# PM12_CDCE62005.net
KiCad netlist of a schematic drawn in Altium Designer
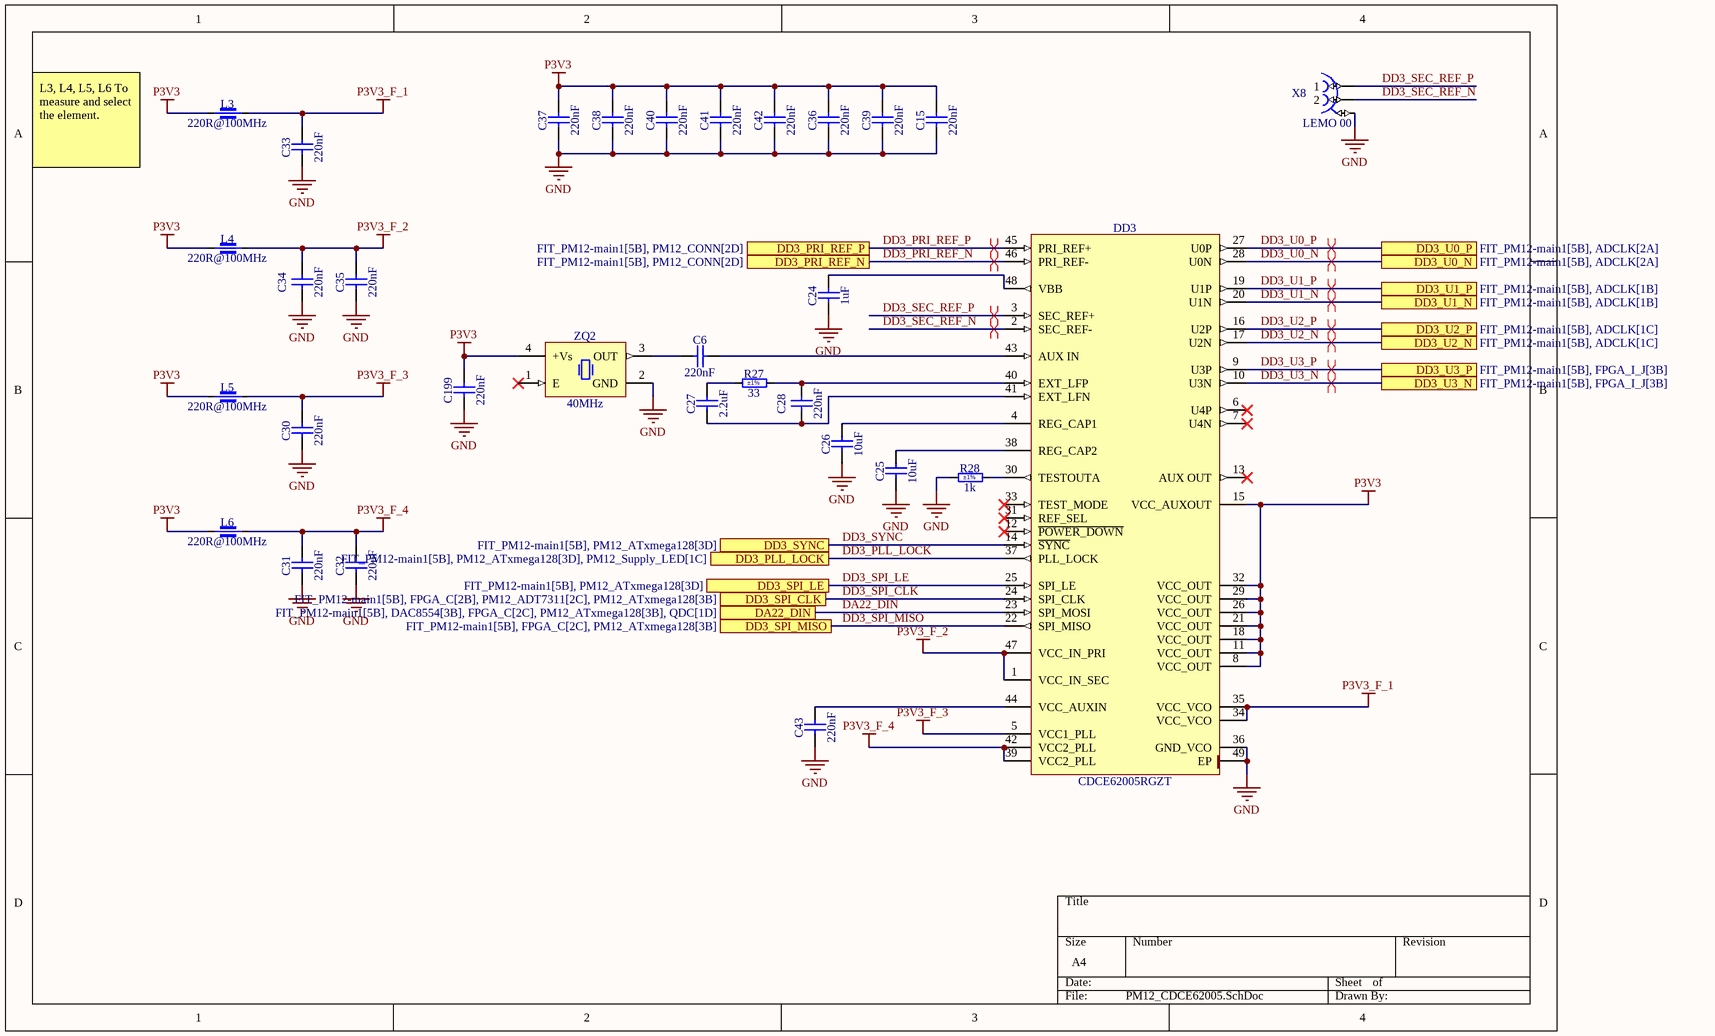
[diagram p0: PM12_CDCE62005.SchDoc]

(export (version "E")
  (design (tool "Eeschema 10.0.6"))
  (components
    (comp (ref "C6")
      (value "220nF")
      (footprint "CAPC2012X135N")
      (description "Non-polarised capacitor")
      (fields
        (field (name "PART NUMBER") "CC0805_220NF_50V_10%_X7R")
        (field (name "VOLTAGE") "50V")
        (field (name "AUTHOR") "CERN DEM JLC")
      )
      (libsource (lib "Capacitors") (part "Capacitor - non polarized"))
    )
    (comp (ref "C15")
      (value "220nF")
      (footprint "CAPC2012X135N")
      (description "Non-polarised capacitor")
      (fields
        (field (name "PART NUMBER") "CC0805_220NF_50V_10%_X7R")
        (field (name "VOLTAGE") "50V")
        (field (name "AUTHOR") "CERN DEM JLC")
      )
      (libsource (lib "Capacitors") (part "Capacitor - non polarized"))
    )
    (comp (ref "C24")
      (value "1uF")
      (footprint "CAPC2012X140N")
      (description "Non-polarised capacitor")
      (fields
        (field (name "PART NUMBER") "CC0805_1UF_25V_10%_X7R")
        (field (name "VOLTAGE") "25V")
        (field (name "AUTHOR") "CERN DEM JLC")
      )
      (libsource (lib "Capacitors") (part "Capacitor - non polarized"))
    )
    (comp (ref "C25")
      (value "10uF")
      (footprint "CAPC2012X145N")
      (description "Non-polarised capacitor")
      (fields
        (field (name "PART NUMBER") "CC0805_10UF_25V_10%_X7R")
        (field (name "VOLTAGE") "25V")
        (field (name "AUTHOR") "CERN DEM HF")
      )
      (libsource (lib "Capacitors") (part "Capacitor - non polarized"))
    )
    (comp (ref "C26")
      (value "10uF")
      (footprint "CAPC2012X145N")
      (description "Non-polarised capacitor")
      (fields
        (field (name "PART NUMBER") "CC0805_10UF_25V_10%_X7R")
        (field (name "VOLTAGE") "25V")
        (field (name "AUTHOR") "CERN DEM HF")
      )
      (libsource (lib "Capacitors") (part "Capacitor - non polarized"))
    )
    (comp (ref "C27")
      (value "2.2uF")
      (footprint "CAPC2012X140N")
      (description "Non-polarised capacitor")
      (fields
        (field (name "PART NUMBER") "CC0805_2.2UF_50V_10%_X7R")
        (field (name "VOLTAGE") "50V")
        (field (name "AUTHOR") "CERN DEM JLC")
      )
      (libsource (lib "Capacitors") (part "Capacitor - non polarized"))
    )
    (comp (ref "C28")
      (value "220nF")
      (footprint "CAPC2012X135N")
      (description "Non-polarised capacitor")
      (fields
        (field (name "PART NUMBER") "CC0805_220NF_50V_10%_X7R")
        (field (name "VOLTAGE") "50V")
        (field (name "AUTHOR") "CERN DEM JLC")
      )
      (libsource (lib "Capacitors") (part "Capacitor - non polarized"))
    )
    (comp (ref "C30")
      (value "220nF")
      (footprint "CAPC2012X135N")
      (description "Non-polarised capacitor")
      (fields
        (field (name "PART NUMBER") "CC0805_220NF_50V_10%_X7R")
        (field (name "VOLTAGE") "50V")
        (field (name "AUTHOR") "CERN DEM JLC")
      )
      (libsource (lib "Capacitors") (part "Capacitor - non polarized"))
    )
    (comp (ref "C31")
      (value "220nF")
      (footprint "CAPC2012X135N")
      (description "Non-polarised capacitor")
      (fields
        (field (name "PART NUMBER") "CC0805_220NF_50V_10%_X7R")
        (field (name "VOLTAGE") "50V")
        (field (name "AUTHOR") "CERN DEM JLC")
      )
      (libsource (lib "Capacitors") (part "Capacitor - non polarized"))
    )
    (comp (ref "C32")
      (value "220nF")
      (footprint "CAPC2012X135N")
      (description "Non-polarised capacitor")
      (fields
        (field (name "PART NUMBER") "CC0805_220NF_50V_10%_X7R")
        (field (name "VOLTAGE") "50V")
        (field (name "AUTHOR") "CERN DEM JLC")
      )
      (libsource (lib "Capacitors") (part "Capacitor - non polarized"))
    )
    (comp (ref "C33")
      (value "220nF")
      (footprint "CAPC2012X135N")
      (description "Non-polarised capacitor")
      (fields
        (field (name "PART NUMBER") "CC0805_220NF_50V_10%_X7R")
        (field (name "VOLTAGE") "50V")
        (field (name "AUTHOR") "CERN DEM JLC")
      )
      (libsource (lib "Capacitors") (part "Capacitor - non polarized"))
    )
    (comp (ref "C34")
      (value "220nF")
      (footprint "CAPC2012X135N")
      (description "Non-polarised capacitor")
      (fields
        (field (name "PART NUMBER") "CC0805_220NF_50V_10%_X7R")
        (field (name "VOLTAGE") "50V")
        (field (name "AUTHOR") "CERN DEM JLC")
      )
      (libsource (lib "Capacitors") (part "Capacitor - non polarized"))
    )
    (comp (ref "C35")
      (value "220nF")
      (footprint "CAPC2012X135N")
      (description "Non-polarised capacitor")
      (fields
        (field (name "PART NUMBER") "CC0805_220NF_50V_10%_X7R")
        (field (name "VOLTAGE") "50V")
        (field (name "AUTHOR") "CERN DEM JLC")
      )
      (libsource (lib "Capacitors") (part "Capacitor - non polarized"))
    )
    (comp (ref "C36")
      (value "220nF")
      (footprint "CAPC2012X135N")
      (description "Non-polarised capacitor")
      (fields
        (field (name "PART NUMBER") "CC0805_220NF_50V_10%_X7R")
        (field (name "VOLTAGE") "50V")
        (field (name "AUTHOR") "CERN DEM JLC")
      )
      (libsource (lib "Capacitors") (part "Capacitor - non polarized"))
    )
    (comp (ref "C37")
      (value "220nF")
      (footprint "CAPC2012X135N")
      (description "Non-polarised capacitor")
      (fields
        (field (name "PART NUMBER") "CC0805_220NF_50V_10%_X7R")
        (field (name "VOLTAGE") "50V")
        (field (name "AUTHOR") "CERN DEM JLC")
      )
      (libsource (lib "Capacitors") (part "Capacitor - non polarized"))
    )
    (comp (ref "C38")
      (value "220nF")
      (footprint "CAPC2012X135N")
      (description "Non-polarised capacitor")
      (fields
        (field (name "PART NUMBER") "CC0805_220NF_50V_10%_X7R")
        (field (name "VOLTAGE") "50V")
        (field (name "AUTHOR") "CERN DEM JLC")
      )
      (libsource (lib "Capacitors") (part "Capacitor - non polarized"))
    )
    (comp (ref "C39")
      (value "220nF")
      (footprint "CAPC2012X135N")
      (description "Non-polarised capacitor")
      (fields
        (field (name "PART NUMBER") "CC0805_220NF_50V_10%_X7R")
        (field (name "VOLTAGE") "50V")
        (field (name "AUTHOR") "CERN DEM JLC")
      )
      (libsource (lib "Capacitors") (part "Capacitor - non polarized"))
    )
    (comp (ref "C40")
      (value "220nF")
      (footprint "CAPC2012X135N")
      (description "Non-polarised capacitor")
      (fields
        (field (name "PART NUMBER") "CC0805_220NF_50V_10%_X7R")
        (field (name "VOLTAGE") "50V")
        (field (name "AUTHOR") "CERN DEM JLC")
      )
      (libsource (lib "Capacitors") (part "Capacitor - non polarized"))
    )
    (comp (ref "C41")
      (value "220nF")
      (footprint "CAPC2012X135N")
      (description "Non-polarised capacitor")
      (fields
        (field (name "PART NUMBER") "CC0805_220NF_50V_10%_X7R")
        (field (name "VOLTAGE") "50V")
        (field (name "AUTHOR") "CERN DEM JLC")
      )
      (libsource (lib "Capacitors") (part "Capacitor - non polarized"))
    )
    (comp (ref "C42")
      (value "220nF")
      (footprint "CAPC2012X135N")
      (description "Non-polarised capacitor")
      (fields
        (field (name "PART NUMBER") "CC0805_220NF_50V_10%_X7R")
        (field (name "VOLTAGE") "50V")
        (field (name "AUTHOR") "CERN DEM JLC")
      )
      (libsource (lib "Capacitors") (part "Capacitor - non polarized"))
    )
    (comp (ref "C43")
      (value "220nF")
      (footprint "CAPC2012X135N")
      (description "Non-polarised capacitor")
      (fields
        (field (name "PART NUMBER") "CC0805_220NF_50V_10%_X7R")
        (field (name "VOLTAGE") "50V")
        (field (name "AUTHOR") "CERN DEM JLC")
      )
      (libsource (lib "Capacitors") (part "Capacitor - non polarized"))
    )
    (comp (ref "C199")
      (value "220nF")
      (footprint "CAPC2012X135N")
      (description "Non-polarised capacitor")
      (fields
        (field (name "PART NUMBER") "CC0805_220NF_50V_10%_X7R")
        (field (name "VOLTAGE") "50V")
        (field (name "AUTHOR") "CERN DEM JLC")
      )
      (libsource (lib "Capacitors") (part "Capacitor - non polarized"))
    )
    (comp (ref "DD3")
      (value "CDCE62005RGZT")
      (footprint "QFN50P700X700X100-49N-S570")
      (description "5/10 Outputs Clock Generator/Jitter Cleaner with Integrated Dual VCO")
      (fields
        (field (name "MANUFACTURER") "TEXAS INSTRUMENTS")
        (field (name "MANUFACTURER PART NUMBER") "CDCE62005RGZ")
        (field (name "AUTHOR") "CERN DEM JLC")
      )
      (libsource (lib "ICs And Semiconductors") (part "CDCE62005RGZT"))
    )
    (comp (ref "L3")
      (value "220R@100MHz")
      (footprint "INDC2012X105N")
      (fields
        (field (name "PART NUMBER") "IND0805_TDK_MPZ2012S221A")
        (field (name "POWER") "3A")
        (field (name "TOLERANCE") "±25%")
        (field (name "AUTHOR") "CERN DEM HF")
      )
      (libsource (lib "Inductors & Transformers") (part "Ferrite Bead"))
    )
    (comp (ref "L4")
      (value "220R@100MHz")
      (footprint "INDC2012X105N")
      (fields
        (field (name "PART NUMBER") "IND0805_TDK_MPZ2012S221A")
        (field (name "POWER") "3A")
        (field (name "TOLERANCE") "±25%")
        (field (name "AUTHOR") "CERN DEM HF")
      )
      (libsource (lib "Inductors & Transformers") (part "Ferrite Bead"))
    )
    (comp (ref "L5")
      (value "220R@100MHz")
      (footprint "INDC2012X105N")
      (fields
        (field (name "PART NUMBER") "IND0805_TDK_MPZ2012S221A")
        (field (name "POWER") "3A")
        (field (name "TOLERANCE") "±25%")
        (field (name "AUTHOR") "CERN DEM HF")
      )
      (libsource (lib "Inductors & Transformers") (part "Ferrite Bead"))
    )
    (comp (ref "L6")
      (value "220R@100MHz")
      (footprint "INDC2012X105N")
      (fields
        (field (name "PART NUMBER") "IND0805_TDK_MPZ2012S221A")
        (field (name "POWER") "3A")
        (field (name "TOLERANCE") "±25%")
        (field (name "AUTHOR") "CERN DEM HF")
      )
      (libsource (lib "Inductors & Transformers") (part "Ferrite Bead"))
    )
    (comp (ref "R27")
      (value "33")
      (footprint "RESC2012X60N")
      (description "Resistor - 1%")
      (fields
        (field (name "TOLERANCE") "±1%")
        (field (name "PART NUMBER") "R0805_33R_1%_0.125W_100PPM")
        (field (name "POWER") "0.125W")
        (field (name "AUTHOR") "CERN DEM JLC")
      )
      (libsource (lib "Resistors") (part "Resistor - 1%"))
    )
    (comp (ref "R28")
      (value "1k")
      (footprint "RESC2012X60N")
      (description "Resistor - 1%")
      (fields
        (field (name "TOLERANCE") "±1%")
        (field (name "PART NUMBER") "R0805_1K_1%_0.125W_100PPM")
        (field (name "POWER") "0.125W")
        (field (name "AUTHOR") "CERN DEM JLC")
      )
      (libsource (lib "Resistors") (part "Resistor - 1%"))
    )
    (comp (ref "X8")
      (value "LEMO 00")
      (footprint "LEMO_EPG.00.302.NLN")
      (fields
        (field (name "PART NUMBER") "LEMO_EPG.00.302.NLN")
        (field (name "MANUFACTURER") "LEMO")
        (field (name "MANUFACTURER PART NUMBER") "EPG.00.302.NLN")
        (field (name "AUTHOR") "CERN DEM JLC")
      )
      (libsource (lib "Connectors") (part "Coax_2Female_1Shield"))
    )
    (comp (ref "ZQ2")
      (value "40MHz")
      (footprint "OSC_IQD_CFPS-73")
      (description "Oscillator 4 pins 1=E 2=GND 3=OUT 4=+Vs")
      (fields
        (field (name "PART NUMBER") "OSC_40MHZ_IQD_LFSPXO018042")
        (field (name "MANUFACTURER") "IQD FREQUENCY PRODUCTS")
        (field (name "AUTHOR") "CERN DEM JLC")
      )
      (libsource (lib "ICs And Semiconductors") (part "Oscillator 1E 2GND 3OUT 4Vs"))
    )
  )
  (nets
    (net (code "1") (name "/DA22_DIN") (class "Default")
      (node (ref "DD3") (pin "23") (pinfunction "SPI_MOSI_23") (pintype "input"))
    )
    (net (code "2") (name "/DD3_PLL_LOCK") (class "Default")
      (node (ref "DD3") (pin "37") (pinfunction "PLL_LOCK_37") (pintype "output"))
    )
    (net (code "3") (name "/DD3_PRI_REF_N") (class "Default")
      (node (ref "DD3") (pin "46") (pinfunction "PRI_REF-_46") (pintype "input"))
    )
    (net (code "4") (name "/DD3_PRI_REF_P") (class "Default")
      (node (ref "DD3") (pin "45") (pinfunction "PRI_REF+_45") (pintype "input"))
    )
    (net (code "5") (name "/DD3_SEC_REF_N") (class "Default")
      (node (ref "DD3") (pin "2") (pinfunction "SEC_REF-_2") (pintype "input"))
      (node (ref "X8") (pin "2") (pinfunction "2_2") (pintype "bidirectional"))
    )
    (net (code "6") (name "/DD3_SEC_REF_P") (class "Default")
      (node (ref "DD3") (pin "3") (pinfunction "SEC_REF+_3") (pintype "input"))
      (node (ref "X8") (pin "1") (pinfunction "1_1") (pintype "bidirectional"))
    )
    (net (code "7") (name "/DD3_SPI_CLK") (class "Default")
      (node (ref "DD3") (pin "24") (pinfunction "SPI_CLK_24") (pintype "input"))
    )
    (net (code "8") (name "/DD3_SPI_LE") (class "Default")
      (node (ref "DD3") (pin "25") (pinfunction "SPI_LE_25") (pintype "input"))
    )
    (net (code "9") (name "/DD3_SPI_MISO") (class "Default")
      (node (ref "DD3") (pin "22") (pinfunction "SPI_MISO_22") (pintype "output"))
    )
    (net (code "10") (name "/DD3_SYNC") (class "Default")
      (node (ref "DD3") (pin "14") (pinfunction "~{SYNC}_14") (pintype "input"))
    )
    (net (code "11") (name "/DD3_U0_N") (class "Default")
      (node (ref "DD3") (pin "28") (pinfunction "U0N_28") (pintype "output"))
    )
    (net (code "12") (name "/DD3_U0_P") (class "Default")
      (node (ref "DD3") (pin "27") (pinfunction "U0P_27") (pintype "output"))
    )
    (net (code "13") (name "/DD3_U1_N") (class "Default")
      (node (ref "DD3") (pin "20") (pinfunction "U1N_20") (pintype "output"))
    )
    (net (code "14") (name "/DD3_U1_P") (class "Default")
      (node (ref "DD3") (pin "19") (pinfunction "U1P_19") (pintype "output"))
    )
    (net (code "15") (name "/DD3_U2_N") (class "Default")
      (node (ref "DD3") (pin "17") (pinfunction "U2N_17") (pintype "output"))
    )
    (net (code "16") (name "/DD3_U2_P") (class "Default")
      (node (ref "DD3") (pin "16") (pinfunction "U2P_16") (pintype "output"))
    )
    (net (code "17") (name "/DD3_U3_N") (class "Default")
      (node (ref "DD3") (pin "10") (pinfunction "U3N_10") (pintype "output"))
    )
    (net (code "18") (name "/DD3_U3_P") (class "Default")
      (node (ref "DD3") (pin "9") (pinfunction "U3P_9") (pintype "output"))
    )
    (net (code "19") (name "GND") (class "Default")
      (node (ref "C15") (pin "1") (pinfunction "1_1") (pintype "passive"))
      (node (ref "C199") (pin "1") (pinfunction "1_1") (pintype "passive"))
      (node (ref "C24") (pin "1") (pinfunction "1_1") (pintype "passive"))
      (node (ref "C25") (pin "1") (pinfunction "1_1") (pintype "passive"))
      (node (ref "C26") (pin "1") (pinfunction "1_1") (pintype "passive"))
      (node (ref "C30") (pin "1") (pinfunction "1_1") (pintype "passive"))
      (node (ref "C31") (pin "1") (pinfunction "1_1") (pintype "passive"))
      (node (ref "C32") (pin "1") (pinfunction "1_1") (pintype "passive"))
      (node (ref "C33") (pin "1") (pinfunction "1_1") (pintype "passive"))
      (node (ref "C34") (pin "1") (pinfunction "1_1") (pintype "passive"))
      (node (ref "C35") (pin "1") (pinfunction "1_1") (pintype "passive"))
      (node (ref "C36") (pin "1") (pinfunction "1_1") (pintype "passive"))
      (node (ref "C37") (pin "1") (pinfunction "1_1") (pintype "passive"))
      (node (ref "C38") (pin "1") (pinfunction "1_1") (pintype "passive"))
      (node (ref "C39") (pin "1") (pinfunction "1_1") (pintype "passive"))
      (node (ref "C40") (pin "1") (pinfunction "1_1") (pintype "passive"))
      (node (ref "C41") (pin "1") (pinfunction "1_1") (pintype "passive"))
      (node (ref "C42") (pin "1") (pinfunction "1_1") (pintype "passive"))
      (node (ref "C43") (pin "1") (pinfunction "1_1") (pintype "passive"))
      (node (ref "DD3") (pin "36") (pinfunction "GND_VCO_36") (pintype "power_in"))
      (node (ref "DD3") (pin "49") (pinfunction "EP_49") (pintype "power_in"))
      (node (ref "R28") (pin "1") (pinfunction "1_1") (pintype "passive"))
      (node (ref "X8") (pin "3") (pinfunction "3_3") (pintype "bidirectional"))
      (node (ref "ZQ2") (pin "2") (pinfunction "GND_2") (pintype "power_in"))
    )
    (net (code "20") (name "Net-(C27-Pad2)") (class "Default")
      (node (ref "C27") (pin "2") (pinfunction "2_2") (pintype "passive"))
      (node (ref "R27") (pin "1") (pinfunction "1_1") (pintype "passive"))
    )
    (net (code "21") (name "Net-(DD3-AUX_IN)") (class "Default")
      (node (ref "C6") (pin "2") (pinfunction "2_2") (pintype "passive"))
      (node (ref "DD3") (pin "43") (pinfunction "AUX_IN_43") (pintype "input"))
    )
    (net (code "22") (name "Net-(DD3-EXT_LFN)") (class "Default")
      (node (ref "C27") (pin "1") (pinfunction "1_1") (pintype "passive"))
      (node (ref "C28") (pin "1") (pinfunction "1_1") (pintype "passive"))
      (node (ref "DD3") (pin "41") (pinfunction "EXT_LFN_41") (pintype "input"))
    )
    (net (code "23") (name "Net-(DD3-EXT_LFP)") (class "Default")
      (node (ref "C28") (pin "2") (pinfunction "2_2") (pintype "passive"))
      (node (ref "DD3") (pin "40") (pinfunction "EXT_LFP_40") (pintype "input"))
      (node (ref "R27") (pin "2") (pinfunction "2_2") (pintype "passive"))
    )
    (net (code "24") (name "Net-(DD3-REG_CAP1)") (class "Default")
      (node (ref "C26") (pin "2") (pinfunction "2_2") (pintype "passive"))
      (node (ref "DD3") (pin "4") (pinfunction "REG_CAP1_4") (pintype "passive"))
    )
    (net (code "25") (name "Net-(DD3-REG_CAP2)") (class "Default")
      (node (ref "C25") (pin "2") (pinfunction "2_2") (pintype "passive"))
      (node (ref "DD3") (pin "38") (pinfunction "REG_CAP2_38") (pintype "passive"))
    )
    (net (code "26") (name "Net-(DD3-TESTOUTA)") (class "Default")
      (node (ref "DD3") (pin "30") (pinfunction "TESTOUTA_30") (pintype "output"))
      (node (ref "R28") (pin "2") (pinfunction "2_2") (pintype "passive"))
    )
    (net (code "27") (name "Net-(DD3-VBB)") (class "Default")
      (node (ref "C24") (pin "2") (pinfunction "2_2") (pintype "passive"))
      (node (ref "DD3") (pin "48") (pinfunction "VBB_48") (pintype "output"))
    )
    (net (code "28") (name "Net-(DD3-VCC_AUXIN)") (class "Default")
      (node (ref "C43") (pin "2") (pinfunction "2_2") (pintype "passive"))
      (node (ref "DD3") (pin "44") (pinfunction "VCC_AUXIN_44") (pintype "power_in"))
    )
    (net (code "29") (name "Net-(ZQ2-OUT)") (class "Default")
      (node (ref "C6") (pin "1") (pinfunction "1_1") (pintype "passive"))
      (node (ref "ZQ2") (pin "3") (pinfunction "OUT_3") (pintype "output"))
    )
    (net (code "30") (name "P3V3") (class "Default")
      (node (ref "C15") (pin "2") (pinfunction "2_2") (pintype "passive"))
      (node (ref "C199") (pin "2") (pinfunction "2_2") (pintype "passive"))
      (node (ref "C36") (pin "2") (pinfunction "2_2") (pintype "passive"))
      (node (ref "C37") (pin "2") (pinfunction "2_2") (pintype "passive"))
      (node (ref "C38") (pin "2") (pinfunction "2_2") (pintype "passive"))
      (node (ref "C39") (pin "2") (pinfunction "2_2") (pintype "passive"))
      (node (ref "C40") (pin "2") (pinfunction "2_2") (pintype "passive"))
      (node (ref "C41") (pin "2") (pinfunction "2_2") (pintype "passive"))
      (node (ref "C42") (pin "2") (pinfunction "2_2") (pintype "passive"))
      (node (ref "DD3") (pin "11") (pinfunction "VCC_OUT_11") (pintype "power_in"))
      (node (ref "DD3") (pin "15") (pinfunction "VCC_AUXOUT_15") (pintype "power_in"))
      (node (ref "DD3") (pin "18") (pinfunction "VCC_OUT_18") (pintype "power_in"))
      (node (ref "DD3") (pin "21") (pinfunction "VCC_OUT_21") (pintype "power_in"))
      (node (ref "DD3") (pin "26") (pinfunction "VCC_OUT_26") (pintype "power_in"))
      (node (ref "DD3") (pin "29") (pinfunction "VCC_OUT_29") (pintype "power_in"))
      (node (ref "DD3") (pin "32") (pinfunction "VCC_OUT_32") (pintype "power_in"))
      (node (ref "DD3") (pin "8") (pinfunction "VCC_OUT_8") (pintype "power_in"))
      (node (ref "L3") (pin "1") (pinfunction "1_1") (pintype "passive"))
      (node (ref "L4") (pin "1") (pinfunction "1_1") (pintype "passive"))
      (node (ref "L5") (pin "1") (pinfunction "1_1") (pintype "passive"))
      (node (ref "L6") (pin "1") (pinfunction "1_1") (pintype "passive"))
      (node (ref "ZQ2") (pin "4") (pinfunction "+Vs_4") (pintype "power_in"))
    )
    (net (code "31") (name "P3V3_F_1") (class "Default")
      (node (ref "C33") (pin "2") (pinfunction "2_2") (pintype "passive"))
      (node (ref "DD3") (pin "34") (pinfunction "VCC_VCO_34") (pintype "power_in"))
      (node (ref "DD3") (pin "35") (pinfunction "VCC_VCO_35") (pintype "power_in"))
      (node (ref "L3") (pin "2") (pinfunction "2_2") (pintype "passive"))
    )
    (net (code "32") (name "P3V3_F_2") (class "Default")
      (node (ref "C34") (pin "2") (pinfunction "2_2") (pintype "passive"))
      (node (ref "C35") (pin "2") (pinfunction "2_2") (pintype "passive"))
      (node (ref "DD3") (pin "1") (pinfunction "VCC_IN_SEC_1") (pintype "power_in"))
      (node (ref "DD3") (pin "47") (pinfunction "VCC_IN_PRI_47") (pintype "power_in"))
      (node (ref "L4") (pin "2") (pinfunction "2_2") (pintype "passive"))
    )
    (net (code "33") (name "P3V3_F_3") (class "Default")
      (node (ref "C30") (pin "2") (pinfunction "2_2") (pintype "passive"))
      (node (ref "DD3") (pin "5") (pinfunction "VCC1_PLL_5") (pintype "power_in"))
      (node (ref "L5") (pin "2") (pinfunction "2_2") (pintype "passive"))
    )
    (net (code "34") (name "P3V3_F_4") (class "Default")
      (node (ref "C31") (pin "2") (pinfunction "2_2") (pintype "passive"))
      (node (ref "C32") (pin "2") (pinfunction "2_2") (pintype "passive"))
      (node (ref "DD3") (pin "39") (pinfunction "VCC2_PLL_39") (pintype "power_in"))
      (node (ref "DD3") (pin "42") (pinfunction "VCC2_PLL_42") (pintype "power_in"))
      (node (ref "L6") (pin "2") (pinfunction "2_2") (pintype "passive"))
    )
    (net (code "35") (name "unconnected-(DD3-AUX_OUT-Pad13)") (class "Default")
      (node (ref "DD3") (pin "13") (pinfunction "AUX_OUT_13") (pintype "output+no_connect"))
    )
    (net (code "36") (name "unconnected-(DD3-REF_SEL-Pad31)") (class "Default")
      (node (ref "DD3") (pin "31") (pinfunction "REF_SEL_31") (pintype "input+no_connect"))
    )
    (net (code "37") (name "unconnected-(DD3-TEST_MODE-Pad33)") (class "Default")
      (node (ref "DD3") (pin "33") (pinfunction "TEST_MODE_33") (pintype "input+no_connect"))
    )
    (net (code "38") (name "unconnected-(DD3-U4N-Pad7)") (class "Default")
      (node (ref "DD3") (pin "7") (pinfunction "U4N_7") (pintype "output+no_connect"))
    )
    (net (code "39") (name "unconnected-(DD3-U4P-Pad6)") (class "Default")
      (node (ref "DD3") (pin "6") (pinfunction "U4P_6") (pintype "output+no_connect"))
    )
    (net (code "40") (name "unconnected-(DD3-~{POWER_DOWN}-Pad12)") (class "Default")
      (node (ref "DD3") (pin "12") (pinfunction "~{POWER_DOWN}_12") (pintype "input+no_connect"))
    )
    (net (code "41") (name "unconnected-(ZQ2-E-Pad1)") (class "Default")
      (node (ref "ZQ2") (pin "1") (pinfunction "E_1") (pintype "input+no_connect"))
    )
  )
)
